# 780-00012-P4_rev2_Sch_M2_Focus_Drive.net
KiCad netlist of a schematic drawn in Altium Designer
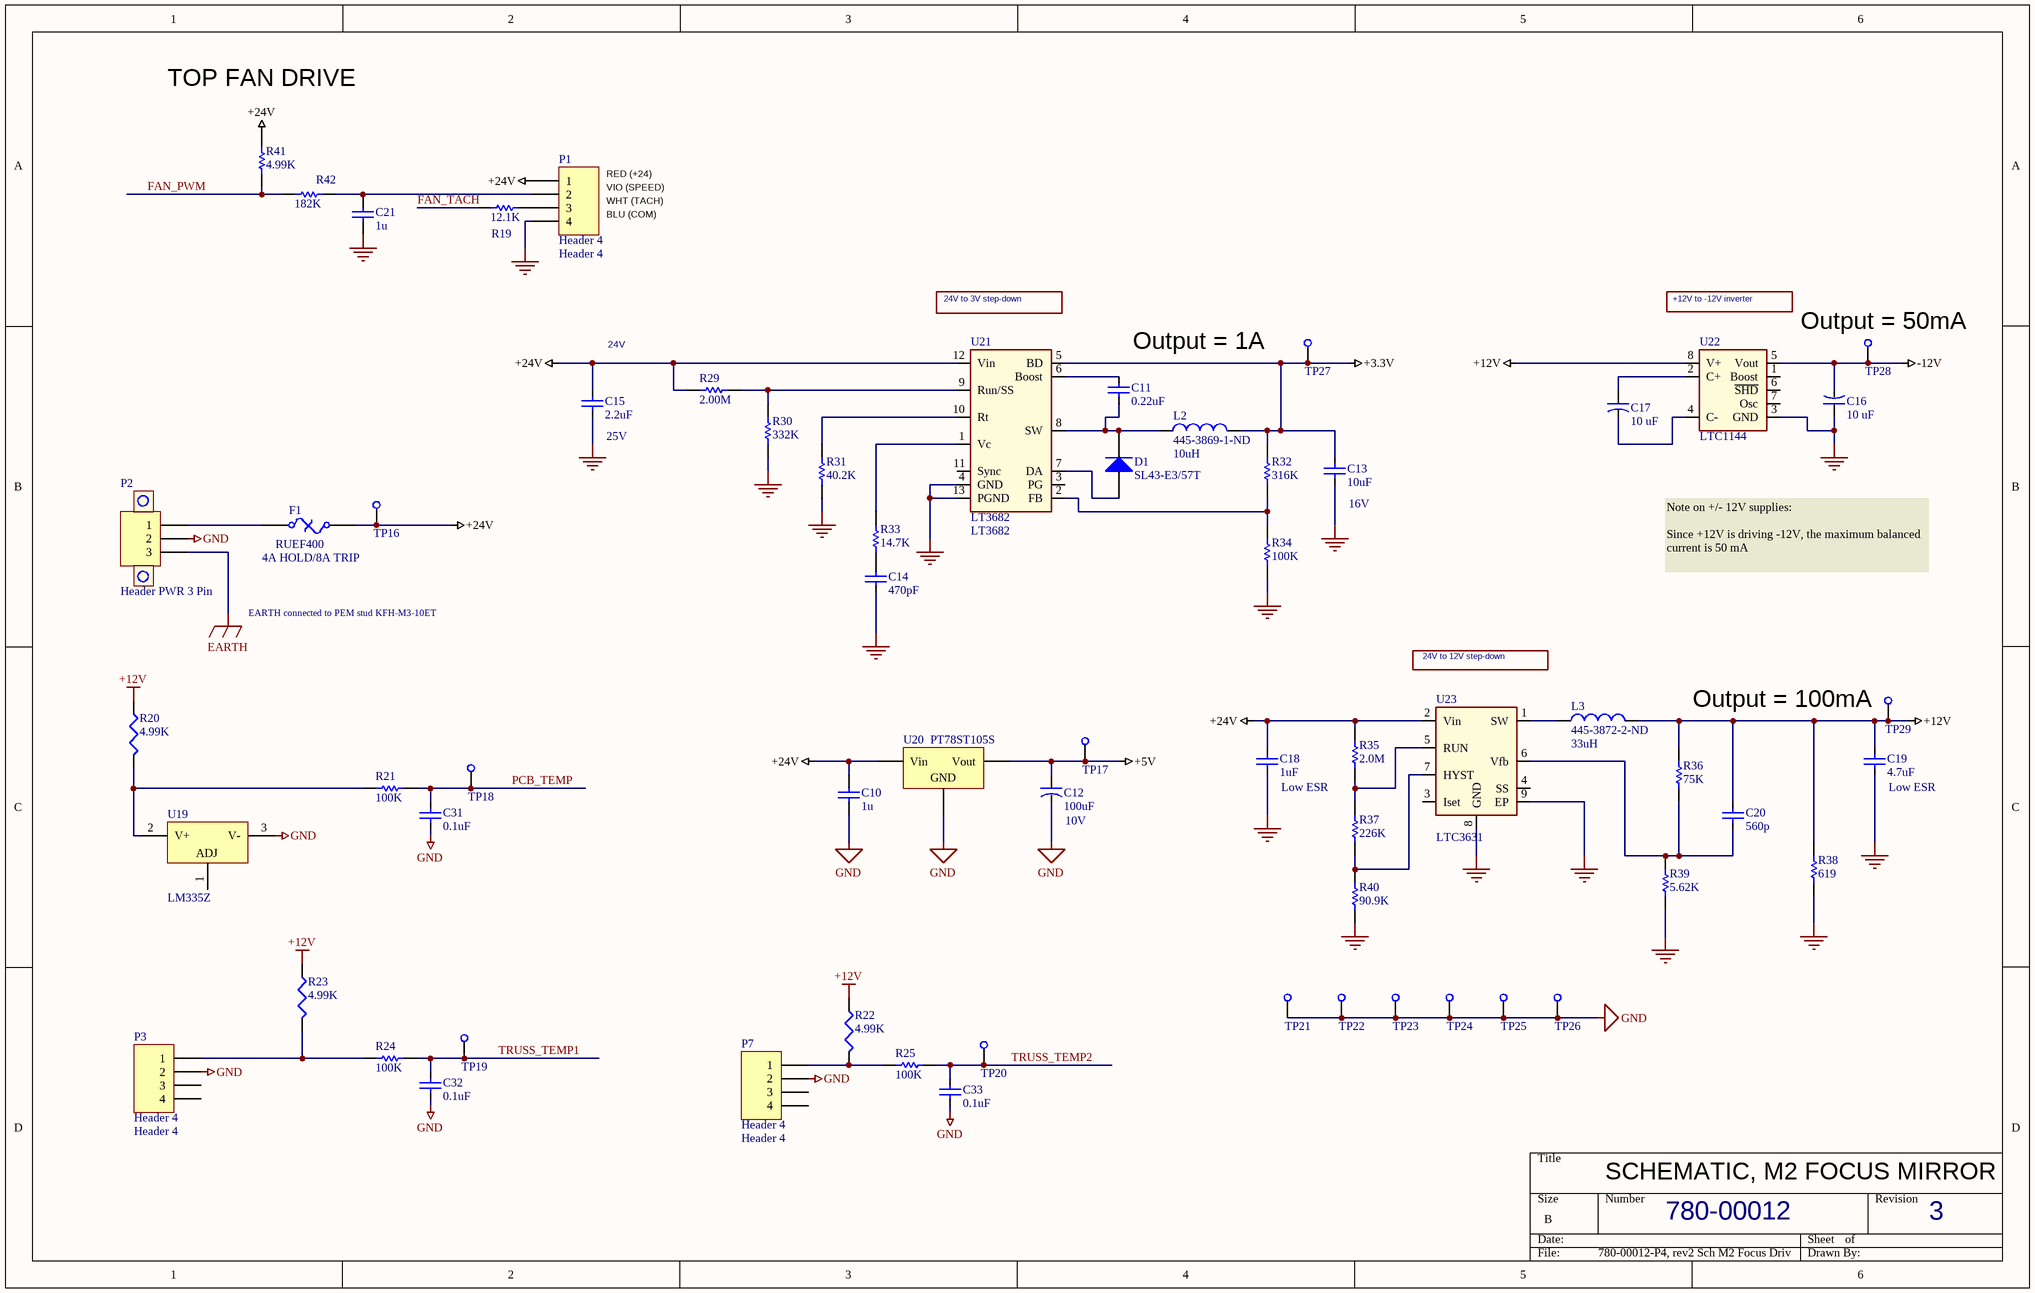
[diagram p0: 780-00012-P4, rev2 Sch M2 Focus Drive.SchDoc]

(export (version "E")
  (design (tool "Eeschema 10.0.6"))
  (components
    (comp (ref "C10")
      (value "1u")
      (footprint "2012[0805]")
      (description "Capacitor")
      (fields (field (name "MANUFACTURER") "Taiyo Yuden"))
      (libsource (lib "Miscellaneous Devices") (part "Cap"))
    )
    (comp (ref "C11")
      (value "0.22uF")
      (footprint "SMD_0805")
      (description "Capacitor")
      (fields (field (name "Comment") "Cap SMD"))
      (libsource (lib "Richs Schematic Components") (part "Cap SMD"))
    )
    (comp (ref "C12")
      (value "10V")
      (footprint "SMD_CAP_7343")
      (description "outline 6.0mm x 3.2mm")
      (fields (field (name "MANUFACTURER") "kEMET") (field (name "ALTIUM_VALUE") "100uF"))
      (libsource (lib "Richs Schematic Components") (part "Cap Tant 35V"))
    )
    (comp (ref "C13")
      (value "16V")
      (footprint "SMD_0805")
      (description "Capacitor")
      (fields (field (name "ALTIUM_VALUE") "10uF"))
      (libsource (lib "Richs Schematic Components") (part "Cap SMD"))
    )
    (comp (ref "C14")
      (value "470pF")
      (footprint "SMD_0805")
      (description "Capacitor")
      (fields (field (name "Comment") "Cap SMD"))
      (libsource (lib "Richs Schematic Components") (part "Cap SMD"))
    )
    (comp (ref "C15")
      (value "25V")
      (footprint "SMD_0805")
      (description "Capacitor")
      (fields (field (name "MANUFACTURER") "Taiyo Yuden") (field (name "ALTIUM_VALUE") "2.2uF"))
      (libsource (lib "Richs Schematic Components") (part "Cap SMD"))
    )
    (comp (ref "C16")
      (value "10 uF")
      (footprint "SMD_CAP_3216")
      (description "outline 3.2mm x 1.6mm")
      (fields (field (name "MANUFACTURER") "KEMET") (field (name "Comment") "16V"))
      (libsource (lib "Richs Schematic Components") (part "Cap Tant 16V"))
    )
    (comp (ref "C17")
      (value "10 uF")
      (footprint "SMD_CAP_3216")
      (description "outline 3.2mm x 1.6mm")
      (fields (field (name "MANUFACTURER") "KEMET") (field (name "Comment") "16V"))
      (libsource (lib "Richs Schematic Components") (part "Cap Tant 16V"))
    )
    (comp (ref "C18")
      (value "Low ESR")
      (footprint "SMD_1206")
      (description "Capacitor")
      (fields (field (name "MANUFACTURER") "TDK") (field (name "ALTIUM_VALUE") "1uF"))
      (libsource (lib "Richs Schematic Components") (part "Cap SMD"))
    )
    (comp (ref "C19")
      (value "Low ESR")
      (footprint "SMD_1206")
      (description "Capacitor")
      (fields (field (name "MANUFACTURER") "TDK") (field (name "ALTIUM_VALUE") "4.7uF"))
      (libsource (lib "Richs Schematic Components") (part "Cap SMD"))
    )
    (comp (ref "C20")
      (value "560p")
      (footprint "SMD_0805")
      (description "Capacitor")
      (fields (field (name "Comment") "Cap SMD"))
      (libsource (lib "Richs Schematic Components") (part "Cap SMD"))
    )
    (comp (ref "C21")
      (value "1u")
      (footprint "2012[0805]")
      (description "Capacitor")
      (fields (field (name "MANUFACTURER") "Taiyo Yuden"))
      (libsource (lib "Miscellaneous Devices") (part "Cap"))
    )
    (comp (ref "C31")
      (value "0.1uF")
      (footprint "SMD_0805")
      (description "Capacitor")
      (fields (field (name "MANUFACTURER") "AVX") (field (name "Comment") "Cap SMD"))
      (libsource (lib "Richs Schematic Components") (part "Cap SMD"))
    )
    (comp (ref "C32")
      (value "0.1uF")
      (footprint "SMD_0805")
      (description "Capacitor")
      (fields (field (name "MANUFACTURER") "AVX") (field (name "Comment") "Cap SMD"))
      (libsource (lib "Richs Schematic Components") (part "Cap SMD"))
    )
    (comp (ref "C33")
      (value "0.1uF")
      (footprint "SMD_0805")
      (description "Capacitor")
      (fields (field (name "MANUFACTURER") "AVX") (field (name "Comment") "Cap SMD"))
      (libsource (lib "Richs Schematic Components") (part "Cap SMD"))
    )
    (comp (ref "D1")
      (value "SL43-E3/57T")
      (footprint "DO-214AB")
      (description "Default Diode")
      (fields (field (name "MANUFACTURER") "Vishay/Dale"))
      (libsource (lib "Miscellaneous Devices") (part "Diode"))
    )
    (comp (ref "F1")
      (value "RUEF400")
      (footprint "PolySwitch Radial 0.2")
      (description "PolySwitch RUE Series")
      (fields
        (field (name "MANUFACTURER") "Tyco Electronics")
        (field (name "ALTIUM_VALUE") "4A HOLD/8A TRIP")
      )
      (libsource (lib "Richs Schematic Components") (part "Fuse Thermal"))
    )
    (comp (ref "L2")
      (value "445-3869-1-ND")
      (footprint "Inductor TDC SLF")
      (description "Inductor")
      (fields (field (name "MANUFACTURER") "TDK") (field (name "ALTIUM_VALUE") "10uH"))
      (libsource (lib "Richs Schematic Components") (part "Inductor SMD 10uH 1.8A"))
    )
    (comp (ref "L3")
      (value "445-3872-2-ND")
      (footprint "Inductor TDC SLF")
      (description "Inductor")
      (fields (field (name "MANUFACTURER") "TDK") (field (name "ALTIUM_VALUE") "33uH"))
      (libsource (lib "Richs Schematic Components") (part "Inductor SMD 10uH 1.8A"))
    )
    (comp (ref "P1")
      (value "Header 4")
      (footprint "HDR1X4 for IDC")
      (description "Header, 4-Pin")
      (fields (field (name "ALTIUM_VALUE") "Header 4"))
      (libsource (lib "Richs Schematic Components") (part "Header 4"))
    )
    (comp (ref "P2")
      (value "Header PWR 3 Pin")
      (footprint "HDR-3 pin w/screw")
      (description "Header, 3-Pin")
      (fields (field (name "MANUFACTURER") "Tyco"))
      (libsource (lib "Richs Schematic Components") (part "Header 3 PWR"))
    )
    (comp (ref "P3")
      (value "Header 4")
      (footprint "HDR1X4 for IDC")
      (description "Header, 4-Pin")
      (fields (field (name "ALTIUM_VALUE") "Header 4"))
      (libsource (lib "") (part "Header 4_1"))
    )
    (comp (ref "P7")
      (value "Header 4")
      (footprint "HDR1X4 for IDC")
      (description "Header, 4-Pin")
      (fields (field (name "ALTIUM_VALUE") "Header 4"))
      (libsource (lib "") (part "Header 4_1"))
    )
    (comp (ref "R19")
      (value "12.1K")
      (footprint "SMD_0805")
      (description "Resistor 0805")
      (fields (field (name "MANUFACTURER") "Vishay/Dale") (field (name "Comment") "Res 0805"))
      (libsource (lib "Richs Schematic Components") (part "Res SMD"))
    )
    (comp (ref "R20")
      (value "4.99K")
      (footprint "smd_0805")
      (description "Resistor")
      (fields (field (name "MANUFACTURER") "DALE") (field (name "Comment") "Res3"))
      (libsource (lib "Miscellaneous Devices") (part "Res3"))
    )
    (comp (ref "R21")
      (value "100K")
      (footprint "SMD_0805")
      (description "Resistor")
      (fields (field (name "MANUFACTURER") "Vishay/Dale") (field (name "Comment") "Res SMD"))
      (libsource (lib "Richs Schematic Components") (part "Res SMD"))
    )
    (comp (ref "R22")
      (value "4.99K")
      (footprint "smd_0805")
      (description "Resistor")
      (fields (field (name "MANUFACTURER") "DALE") (field (name "Comment") "Res3"))
      (libsource (lib "Miscellaneous Devices") (part "Res3"))
    )
    (comp (ref "R23")
      (value "4.99K")
      (footprint "smd_0805")
      (description "Resistor")
      (fields (field (name "MANUFACTURER") "DALE") (field (name "Comment") "Res3"))
      (libsource (lib "Miscellaneous Devices") (part "Res3"))
    )
    (comp (ref "R24")
      (value "100K")
      (footprint "SMD_0805")
      (description "Resistor")
      (fields (field (name "MANUFACTURER") "Vishay/Dale") (field (name "Comment") "Res SMD"))
      (libsource (lib "Richs Schematic Components") (part "Res SMD"))
    )
    (comp (ref "R25")
      (value "100K")
      (footprint "SMD_0805")
      (description "Resistor")
      (fields (field (name "MANUFACTURER") "Vishay/Dale") (field (name "Comment") "Res SMD"))
      (libsource (lib "Richs Schematic Components") (part "Res SMD"))
    )
    (comp (ref "R29")
      (value "2.00M")
      (footprint "SMD_0805")
      (description "Resistor 0805")
      (fields (field (name "MANUFACTURER") "Vishay/Dale") (field (name "Comment") "Res 0805"))
      (libsource (lib "Richs Schematic Components") (part "Res SMD"))
    )
    (comp (ref "R30")
      (value "332K")
      (footprint "SMD_0805")
      (description "Resistor 0805")
      (fields (field (name "MANUFACTURER") "Vishay/Dale") (field (name "Comment") "Res 0805"))
      (libsource (lib "Richs Schematic Components") (part "Res SMD"))
    )
    (comp (ref "R31")
      (value "40.2K")
      (footprint "SMD_0805")
      (description "Resistor 0805")
      (fields (field (name "MANUFACTURER") "Vishay/Dale") (field (name "Comment") "Res 0805"))
      (libsource (lib "Richs Schematic Components") (part "Res SMD"))
    )
    (comp (ref "R32")
      (value "316K")
      (footprint "SMD_0805")
      (description "Resistor 0805")
      (fields (field (name "MANUFACTURER") "Vishay/Dale") (field (name "Comment") "Res 0805"))
      (libsource (lib "Richs Schematic Components") (part "Res SMD"))
    )
    (comp (ref "R33")
      (value "14.7K")
      (footprint "SMD_0805")
      (description "Resistor 0805")
      (fields (field (name "MANUFACTURER") "Vishay/Dale") (field (name "Comment") "Res 0805"))
      (libsource (lib "Richs Schematic Components") (part "Res SMD"))
    )
    (comp (ref "R34")
      (value "100K")
      (footprint "SMD_0805")
      (description "Resistor 0805")
      (fields (field (name "MANUFACTURER") "Vishay/Dale") (field (name "Comment") "Res 0805"))
      (libsource (lib "Richs Schematic Components") (part "Res SMD"))
    )
    (comp (ref "R35")
      (value "2.0M")
      (footprint "SMD_0805")
      (description "Resistor 0805")
      (fields (field (name "MANUFACTURER") "Vishay/Dale") (field (name "Comment") "Res 0805"))
      (libsource (lib "Richs Schematic Components") (part "Res SMD"))
    )
    (comp (ref "R36")
      (value "75K")
      (footprint "SMD_0805")
      (description "Resistor 0805")
      (fields (field (name "MANUFACTURER") "Vishay/Dale") (field (name "Comment") "Res 0805"))
      (libsource (lib "Richs Schematic Components") (part "Res SMD"))
    )
    (comp (ref "R37")
      (value "226K")
      (footprint "SMD_0805")
      (description "Resistor 0805")
      (fields (field (name "MANUFACTURER") "Vishay/Dale") (field (name "Comment") "Res 0805"))
      (libsource (lib "Richs Schematic Components") (part "Res SMD"))
    )
    (comp (ref "R38")
      (value "619")
      (footprint "SMD_0805")
      (description "Resistor 0805")
      (fields (field (name "MANUFACTURER") "Vishay/Dale") (field (name "Comment") "Res 0805"))
      (libsource (lib "Richs Schematic Components") (part "Res SMD"))
    )
    (comp (ref "R39")
      (value "5.62K")
      (footprint "SMD_0805")
      (description "Resistor 0805")
      (fields (field (name "MANUFACTURER") "Vishay/Dale") (field (name "Comment") "Res 0805"))
      (libsource (lib "Richs Schematic Components") (part "Res SMD"))
    )
    (comp (ref "R40")
      (value "90.9K")
      (footprint "SMD_0805")
      (description "Resistor 0805")
      (fields (field (name "MANUFACTURER") "Vishay/Dale") (field (name "Comment") "Res 0805"))
      (libsource (lib "Richs Schematic Components") (part "Res SMD"))
    )
    (comp (ref "R41")
      (value "4.99K")
      (footprint "SMD_0805")
      (description "Resistor 0805")
      (fields (field (name "MANUFACTURER") "Vishay/Dale") (field (name "Comment") "Res 0805"))
      (libsource (lib "Richs Schematic Components") (part "Res SMD"))
    )
    (comp (ref "R42")
      (value "182K")
      (footprint "SMD_0805")
      (description "Resistor 0805")
      (fields (field (name "MANUFACTURER") "Vishay/Dale") (field (name "Comment") "Res 0805"))
      (libsource (lib "Richs Schematic Components") (part "Res SMD"))
    )
    (comp (ref "TP16")
      (value "Test Point SMD")
      (footprint "SMD_TEST POINT")
      (description "SMD loop test point")
      (libsource (lib "Richs Schematic Components") (part "Test Point SMD"))
    )
    (comp (ref "TP17")
      (value "Test Point SMD")
      (footprint "SMD_TEST POINT")
      (description "SMD loop test point")
      (libsource (lib "Richs Schematic Components") (part "Test Point SMD"))
    )
    (comp (ref "TP18")
      (value "Test Point SMD")
      (footprint "SMD_TEST POINT")
      (description "SMD loop test point")
      (libsource (lib "Richs Schematic Components") (part "Test Point SMD"))
    )
    (comp (ref "TP19")
      (value "Test Point SMD")
      (footprint "SMD_TEST POINT")
      (description "SMD loop test point")
      (libsource (lib "Richs Schematic Components") (part "Test Point SMD"))
    )
    (comp (ref "TP20")
      (value "Test Point SMD")
      (footprint "SMD_TEST POINT")
      (description "SMD loop test point")
      (libsource (lib "Richs Schematic Components") (part "Test Point SMD"))
    )
    (comp (ref "TP21")
      (value "Test Point SMD")
      (footprint "SMD_TEST POINT")
      (description "SMD loop test point")
      (libsource (lib "Richs Schematic Components") (part "Test Point SMD"))
    )
    (comp (ref "TP22")
      (value "Test Point SMD")
      (footprint "SMD_TEST POINT")
      (description "SMD loop test point")
      (libsource (lib "Richs Schematic Components") (part "Test Point SMD"))
    )
    (comp (ref "TP23")
      (value "Test Point SMD")
      (footprint "SMD_TEST POINT")
      (description "SMD loop test point")
      (libsource (lib "Richs Schematic Components") (part "Test Point SMD"))
    )
    (comp (ref "TP24")
      (value "Test Point SMD")
      (footprint "SMD_TEST POINT")
      (description "SMD loop test point")
      (libsource (lib "Richs Schematic Components") (part "Test Point SMD"))
    )
    (comp (ref "TP25")
      (value "Test Point SMD")
      (footprint "SMD_TEST POINT")
      (description "SMD loop test point")
      (libsource (lib "Richs Schematic Components") (part "Test Point SMD"))
    )
    (comp (ref "TP26")
      (value "Test Point SMD")
      (footprint "SMD_TEST POINT")
      (description "SMD loop test point")
      (libsource (lib "Richs Schematic Components") (part "Test Point SMD"))
    )
    (comp (ref "TP27")
      (value "Test Point SMD")
      (footprint "SMD_TEST POINT")
      (description "SMD loop test point")
      (libsource (lib "Richs Schematic Components") (part "Test Point SMD"))
    )
    (comp (ref "TP28")
      (value "Test Point SMD")
      (footprint "SMD_TEST POINT")
      (description "SMD loop test point")
      (libsource (lib "Richs Schematic Components") (part "Test Point SMD"))
    )
    (comp (ref "TP29")
      (value "Test Point SMD")
      (footprint "SMD_TEST POINT")
      (description "SMD loop test point")
      (libsource (lib "Richs Schematic Components") (part "Test Point SMD"))
    )
    (comp (ref "U19")
      (value "LM335Z")
      (footprint "Z03A")
      (description "Precision Temperature Sensor")
      (fields (field (name "MANUFACTURER") "National Semiconductor"))
      (libsource (lib "NSC Temperature Sensor") (part "LM335Z"))
    )
    (comp (ref "U20")
      (value "PT78ST105S")
      (footprint "PSIP_3_SMD")
      (description "Voltage Regulator")
      (fields (field (name "MANUFACTURER") "Texas Instruments"))
      (libsource (lib "Miscellaneous Devices") (part "Volt Reg"))
    )
    (comp (ref "U21")
      (value "LT3682")
      (footprint "DD12/DFN12")
      (description "1A uPwr Step-Down switching regulator")
      (fields (field (name "MANUFACTURER") "Linear") (field (name "ALTIUM_VALUE") "LT3682"))
      (libsource (lib "Richs Schematic Components") (part "LT3682"))
    )
    (comp (ref "U22")
      (value "LTC1144")
      (footprint "S8_M")
      (description "IC VOLT CONV SW-CAP W/SHTDN8SOIC")
      (fields (field (name "MANUFACTURER") "Linear"))
      (libsource (lib "Richs Schematic Components") (part "LTC1144"))
    )
    (comp (ref "U23")
      (value "LTC3631")
      (footprint "DD8/DFN8")
      (description "IC CONV STP-DWN ADJ 8-DFN")
      (fields (field (name "MANUFACTURER") "Linear"))
      (libsource (lib "Richs Schematic Components") (part "LTC3631"))
    )
  )
  (nets
    (net (code "1") (name "+3.3V") (class "Default")
      (node (ref "C13") (pin "2") (pinfunction "2_2") (pintype "passive"))
      (node (ref "L2") (pin "2") (pinfunction "2_2") (pintype "passive"))
      (node (ref "R32") (pin "2") (pinfunction "2_2") (pintype "passive"))
      (node (ref "TP27") (pin "1") (pinfunction "TP_1") (pintype "passive"))
      (node (ref "U21") (pin "5") (pinfunction "BD_5") (pintype "passive"))
    )
    (net (code "2") (name "+5V") (class "Default")
      (node (ref "C12") (pin "pos") (pinfunction "1_pos") (pintype "passive"))
      (node (ref "TP17") (pin "1") (pinfunction "TP_1") (pintype "passive"))
      (node (ref "U20") (pin "3") (pinfunction "Vout_3") (pintype "passive"))
    )
    (net (code "3") (name "+12V") (class "Default")
      (node (ref "C19") (pin "2") (pinfunction "2_2") (pintype "passive"))
      (node (ref "C20") (pin "2") (pinfunction "2_2") (pintype "passive"))
      (node (ref "L3") (pin "2") (pinfunction "2_2") (pintype "passive"))
      (node (ref "R20") (pin "1") (pinfunction "1_1") (pintype "passive"))
      (node (ref "R22") (pin "1") (pinfunction "1_1") (pintype "passive"))
      (node (ref "R23") (pin "1") (pinfunction "1_1") (pintype "passive"))
      (node (ref "R36") (pin "2") (pinfunction "2_2") (pintype "passive"))
      (node (ref "R38") (pin "2") (pinfunction "2_2") (pintype "passive"))
      (node (ref "TP29") (pin "1") (pinfunction "TP_1") (pintype "passive"))
      (node (ref "U22") (pin "8") (pinfunction "V+_8") (pintype "power_in"))
    )
    (net (code "4") (name "+24V") (class "Default")
      (node (ref "C10") (pin "1") (pinfunction "1_1") (pintype "passive"))
      (node (ref "C15") (pin "2") (pinfunction "2_2") (pintype "passive"))
      (node (ref "C18") (pin "2") (pinfunction "2_2") (pintype "passive"))
      (node (ref "F1") (pin "2") (pinfunction "2_2") (pintype "passive"))
      (node (ref "P1") (pin "1") (pinfunction "1_1") (pintype "passive"))
      (node (ref "R29") (pin "1") (pinfunction "1_1") (pintype "passive"))
      (node (ref "R35") (pin "2") (pinfunction "2_2") (pintype "passive"))
      (node (ref "R41") (pin "2") (pinfunction "2_2") (pintype "passive"))
      (node (ref "TP16") (pin "1") (pinfunction "TP_1") (pintype "passive"))
      (node (ref "U20") (pin "1") (pinfunction "Vin_1") (pintype "passive"))
      (node (ref "U21") (pin "12") (pinfunction "Vin_12") (pintype "passive"))
      (node (ref "U23") (pin "2") (pinfunction "Vin_2") (pintype "passive"))
    )
    (net (code "5") (name "-12V") (class "Default")
      (node (ref "C16") (pin "2") (pinfunction "2_2") (pintype "passive"))
      (node (ref "TP28") (pin "1") (pinfunction "TP_1") (pintype "passive"))
      (node (ref "U22") (pin "5") (pinfunction "Vout_5") (pintype "passive"))
    )
    (net (code "6") (name "/FAN_PWM") (class "Default")
      (node (ref "R41") (pin "1") (pinfunction "1_1") (pintype "passive"))
      (node (ref "R42") (pin "1") (pinfunction "1_1") (pintype "passive"))
    )
    (net (code "7") (name "/FAN_TACH") (class "Default")
      (node (ref "R19") (pin "1") (pinfunction "1_1") (pintype "passive"))
    )
    (net (code "8") (name "/PCB_TEMP") (class "Default")
      (node (ref "C31") (pin "2") (pinfunction "2_2") (pintype "passive"))
      (node (ref "R21") (pin "1") (pinfunction "1_1") (pintype "passive"))
      (node (ref "TP18") (pin "1") (pinfunction "TP_1") (pintype "passive"))
    )
    (net (code "9") (name "/TRUSS_TEMP1") (class "Default")
      (node (ref "C32") (pin "2") (pinfunction "2_2") (pintype "passive"))
      (node (ref "R24") (pin "1") (pinfunction "1_1") (pintype "passive"))
      (node (ref "TP19") (pin "1") (pinfunction "TP_1") (pintype "passive"))
    )
    (net (code "10") (name "/TRUSS_TEMP2") (class "Default")
      (node (ref "C33") (pin "2") (pinfunction "2_2") (pintype "passive"))
      (node (ref "R25") (pin "1") (pinfunction "1_1") (pintype "passive"))
      (node (ref "TP20") (pin "1") (pinfunction "TP_1") (pintype "passive"))
    )
    (net (code "11") (name "EARTH") (class "Default")
      (node (ref "P2") (pin "3") (pinfunction "3_3") (pintype "passive"))
    )
    (net (code "12") (name "GND") (class "Default")
      (node (ref "C10") (pin "2") (pinfunction "2_2") (pintype "passive"))
      (node (ref "C12") (pin "neg") (pinfunction "2_neg") (pintype "passive"))
      (node (ref "C13") (pin "1") (pinfunction "1_1") (pintype "passive"))
      (node (ref "C14") (pin "1") (pinfunction "1_1") (pintype "passive"))
      (node (ref "C15") (pin "1") (pinfunction "1_1") (pintype "passive"))
      (node (ref "C16") (pin "1") (pinfunction "1_1") (pintype "passive"))
      (node (ref "C18") (pin "1") (pinfunction "1_1") (pintype "passive"))
      (node (ref "C19") (pin "1") (pinfunction "1_1") (pintype "passive"))
      (node (ref "C21") (pin "2") (pinfunction "2_2") (pintype "passive"))
      (node (ref "C31") (pin "1") (pinfunction "1_1") (pintype "passive"))
      (node (ref "C32") (pin "1") (pinfunction "1_1") (pintype "passive"))
      (node (ref "C33") (pin "1") (pinfunction "1_1") (pintype "passive"))
      (node (ref "P1") (pin "4") (pinfunction "4_4") (pintype "passive"))
      (node (ref "P2") (pin "2") (pinfunction "2_2") (pintype "passive"))
      (node (ref "P3") (pin "2") (pinfunction "2_2") (pintype "passive"))
      (node (ref "P7") (pin "2") (pinfunction "2_2") (pintype "passive"))
      (node (ref "R30") (pin "1") (pinfunction "1_1") (pintype "passive"))
      (node (ref "R31") (pin "1") (pinfunction "1_1") (pintype "passive"))
      (node (ref "R34") (pin "1") (pinfunction "1_1") (pintype "passive"))
      (node (ref "R38") (pin "1") (pinfunction "1_1") (pintype "passive"))
      (node (ref "R39") (pin "1") (pinfunction "1_1") (pintype "passive"))
      (node (ref "R40") (pin "1") (pinfunction "1_1") (pintype "passive"))
      (node (ref "TP21") (pin "1") (pinfunction "TP_1") (pintype "passive"))
      (node (ref "TP22") (pin "1") (pinfunction "TP_1") (pintype "passive"))
      (node (ref "TP23") (pin "1") (pinfunction "TP_1") (pintype "passive"))
      (node (ref "TP24") (pin "1") (pinfunction "TP_1") (pintype "passive"))
      (node (ref "TP25") (pin "1") (pinfunction "TP_1") (pintype "passive"))
      (node (ref "TP26") (pin "1") (pinfunction "TP_1") (pintype "passive"))
      (node (ref "U19") (pin "3") (pinfunction "V-_3") (pintype "passive"))
      (node (ref "U20") (pin "2") (pinfunction "GND_2") (pintype "passive"))
      (node (ref "U21") (pin "13") (pinfunction "PGND_13") (pintype "passive"))
      (node (ref "U21") (pin "4") (pinfunction "GND_4") (pintype "power_in"))
      (node (ref "U22") (pin "3") (pinfunction "GND_3") (pintype "passive"))
      (node (ref "U23") (pin "8") (pinfunction "GND_8") (pintype "passive"))
      (node (ref "U23") (pin "9") (pinfunction "EP_9") (pintype "passive"))
    )
    (net (code "13") (name "Net-(C14-Pad2)") (class "Default")
      (node (ref "C14") (pin "2") (pinfunction "2_2") (pintype "passive"))
      (node (ref "R33") (pin "1") (pinfunction "1_1") (pintype "passive"))
    )
    (net (code "14") (name "Net-(C21-Pad1)") (class "Default")
      (node (ref "C21") (pin "1") (pinfunction "1_1") (pintype "passive"))
      (node (ref "P1") (pin "2") (pinfunction "2_2") (pintype "passive"))
      (node (ref "R42") (pin "2") (pinfunction "2_2") (pintype "passive"))
    )
    (net (code "15") (name "Net-(D1-A)") (class "Default")
      (node (ref "D1") (pin "1") (pinfunction "A_1") (pintype "passive"))
      (node (ref "U21") (pin "7") (pinfunction "DA_7") (pintype "passive"))
    )
    (net (code "16") (name "Net-(D1-K)") (class "Default")
      (node (ref "C11") (pin "1") (pinfunction "1_1") (pintype "passive"))
      (node (ref "D1") (pin "2") (pinfunction "K_2") (pintype "passive"))
      (node (ref "L2") (pin "1") (pinfunction "1_1") (pintype "passive"))
      (node (ref "U21") (pin "8") (pinfunction "SW_8") (pintype "passive"))
    )
    (net (code "17") (name "Net-(F1-Pad1)") (class "Default")
      (node (ref "F1") (pin "1") (pinfunction "1_1") (pintype "passive"))
      (node (ref "P2") (pin "1") (pinfunction "1_1") (pintype "passive"))
    )
    (net (code "18") (name "Net-(P1-Pad3)") (class "Default")
      (node (ref "P1") (pin "3") (pinfunction "3_3") (pintype "passive"))
      (node (ref "R19") (pin "2") (pinfunction "2_2") (pintype "passive"))
    )
    (net (code "19") (name "Net-(P3-Pad1)") (class "Default")
      (node (ref "P3") (pin "1") (pinfunction "1_1") (pintype "passive"))
      (node (ref "R23") (pin "2") (pinfunction "2_2") (pintype "passive"))
      (node (ref "R24") (pin "2") (pinfunction "2_2") (pintype "passive"))
    )
    (net (code "20") (name "Net-(P7-Pad1)") (class "Default")
      (node (ref "P7") (pin "1") (pinfunction "1_1") (pintype "passive"))
      (node (ref "R22") (pin "2") (pinfunction "2_2") (pintype "passive"))
      (node (ref "R25") (pin "2") (pinfunction "2_2") (pintype "passive"))
    )
    (net (code "21") (name "Net-(U19-V+)") (class "Default")
      (node (ref "R20") (pin "2") (pinfunction "2_2") (pintype "passive"))
      (node (ref "R21") (pin "2") (pinfunction "2_2") (pintype "passive"))
      (node (ref "U19") (pin "2") (pinfunction "V+_2") (pintype "passive"))
    )
    (net (code "22") (name "Net-(U21-Boost)") (class "Default")
      (node (ref "C11") (pin "2") (pinfunction "2_2") (pintype "passive"))
      (node (ref "U21") (pin "6") (pinfunction "Boost_6") (pintype "passive"))
    )
    (net (code "23") (name "Net-(U21-FB)") (class "Default")
      (node (ref "R32") (pin "1") (pinfunction "1_1") (pintype "passive"))
      (node (ref "R34") (pin "2") (pinfunction "2_2") (pintype "passive"))
      (node (ref "U21") (pin "2") (pinfunction "FB_2") (pintype "passive"))
    )
    (net (code "24") (name "Net-(U21-Rt)") (class "Default")
      (node (ref "R31") (pin "2") (pinfunction "2_2") (pintype "passive"))
      (node (ref "U21") (pin "10") (pinfunction "Rt_10") (pintype "passive"))
    )
    (net (code "25") (name "Net-(U21-Run{slash}SS)") (class "Default")
      (node (ref "R29") (pin "2") (pinfunction "2_2") (pintype "passive"))
      (node (ref "R30") (pin "2") (pinfunction "2_2") (pintype "passive"))
      (node (ref "U21") (pin "9") (pinfunction "Run/SS_9") (pintype "passive"))
    )
    (net (code "26") (name "Net-(U21-Vc)") (class "Default")
      (node (ref "R33") (pin "2") (pinfunction "2_2") (pintype "passive"))
      (node (ref "U21") (pin "1") (pinfunction "Vc_1") (pintype "passive"))
    )
    (net (code "27") (name "Net-(U22-C+)") (class "Default")
      (node (ref "C17") (pin "1") (pinfunction "1_1") (pintype "passive"))
      (node (ref "U22") (pin "2") (pinfunction "C+_2") (pintype "passive"))
    )
    (net (code "28") (name "Net-(U22-C-)") (class "Default")
      (node (ref "C17") (pin "2") (pinfunction "2_2") (pintype "passive"))
      (node (ref "U22") (pin "4") (pinfunction "C-_4") (pintype "passive"))
    )
    (net (code "29") (name "Net-(U23-HYST)") (class "Default")
      (node (ref "R37") (pin "1") (pinfunction "1_1") (pintype "passive"))
      (node (ref "R40") (pin "2") (pinfunction "2_2") (pintype "passive"))
      (node (ref "U23") (pin "7") (pinfunction "HYST_7") (pintype "passive"))
    )
    (net (code "30") (name "Net-(U23-RUN)") (class "Default")
      (node (ref "R35") (pin "1") (pinfunction "1_1") (pintype "passive"))
      (node (ref "R37") (pin "2") (pinfunction "2_2") (pintype "passive"))
      (node (ref "U23") (pin "5") (pinfunction "RUN_5") (pintype "passive"))
    )
    (net (code "31") (name "Net-(U23-SW)") (class "Default")
      (node (ref "L3") (pin "1") (pinfunction "1_1") (pintype "passive"))
      (node (ref "U23") (pin "1") (pinfunction "SW_1") (pintype "passive"))
    )
    (net (code "32") (name "Net-(U23-Vfb)") (class "Default")
      (node (ref "C20") (pin "1") (pinfunction "1_1") (pintype "passive"))
      (node (ref "R36") (pin "1") (pinfunction "1_1") (pintype "passive"))
      (node (ref "R39") (pin "2") (pinfunction "2_2") (pintype "passive"))
      (node (ref "U23") (pin "6") (pinfunction "Vfb_6") (pintype "passive"))
    )
    (net (code "33") (name "SUPPORT") (class "Default")
      (node (ref "U20") (pin "0") (pinfunction "SUPPORT_0") (pintype "passive"))
    )
    (net (code "34") (name "unconnected-(P3-Pad3)") (class "Default")
      (node (ref "P3") (pin "3") (pinfunction "3_3") (pintype "passive"))
    )
    (net (code "35") (name "unconnected-(P3-Pad4)") (class "Default")
      (node (ref "P3") (pin "4") (pinfunction "4_4") (pintype "passive"))
    )
    (net (code "36") (name "unconnected-(P7-Pad3)") (class "Default")
      (node (ref "P7") (pin "3") (pinfunction "3_3") (pintype "passive"))
    )
    (net (code "37") (name "unconnected-(P7-Pad4)") (class "Default")
      (node (ref "P7") (pin "4") (pinfunction "4_4") (pintype "passive"))
    )
    (net (code "38") (name "unconnected-(U19-ADJ-Pad1)") (class "Default")
      (node (ref "U19") (pin "1") (pinfunction "ADJ_1") (pintype "passive"))
    )
    (net (code "39") (name "unconnected-(U21-PG-Pad3)") (class "Default")
      (node (ref "U21") (pin "3") (pinfunction "PG_3") (pintype "passive"))
    )
    (net (code "40") (name "unconnected-(U21-Sync-Pad11)") (class "Default")
      (node (ref "U21") (pin "11") (pinfunction "Sync_11") (pintype "passive"))
    )
    (net (code "41") (name "unconnected-(U22-Boost-Pad1)") (class "Default")
      (node (ref "U22") (pin "1") (pinfunction "Boost_1") (pintype "passive"))
    )
    (net (code "42") (name "unconnected-(U22-Osc-Pad7)") (class "Default")
      (node (ref "U22") (pin "7") (pinfunction "Osc_7") (pintype "passive"))
    )
    (net (code "43") (name "unconnected-(U22-~{SHD}-Pad6)") (class "Default")
      (node (ref "U22") (pin "6") (pinfunction "~{SHD}_6") (pintype "passive"))
    )
    (net (code "44") (name "unconnected-(U23-Iset-Pad3)") (class "Default")
      (node (ref "U23") (pin "3") (pinfunction "Iset_3") (pintype "passive"))
    )
    (net (code "45") (name "unconnected-(U23-SS-Pad4)") (class "Default")
      (node (ref "U23") (pin "4") (pinfunction "SS_4") (pintype "passive"))
    )
  )
)
